# CLK_INPUT.net
KiCad netlist of a schematic drawn in Altium Designer
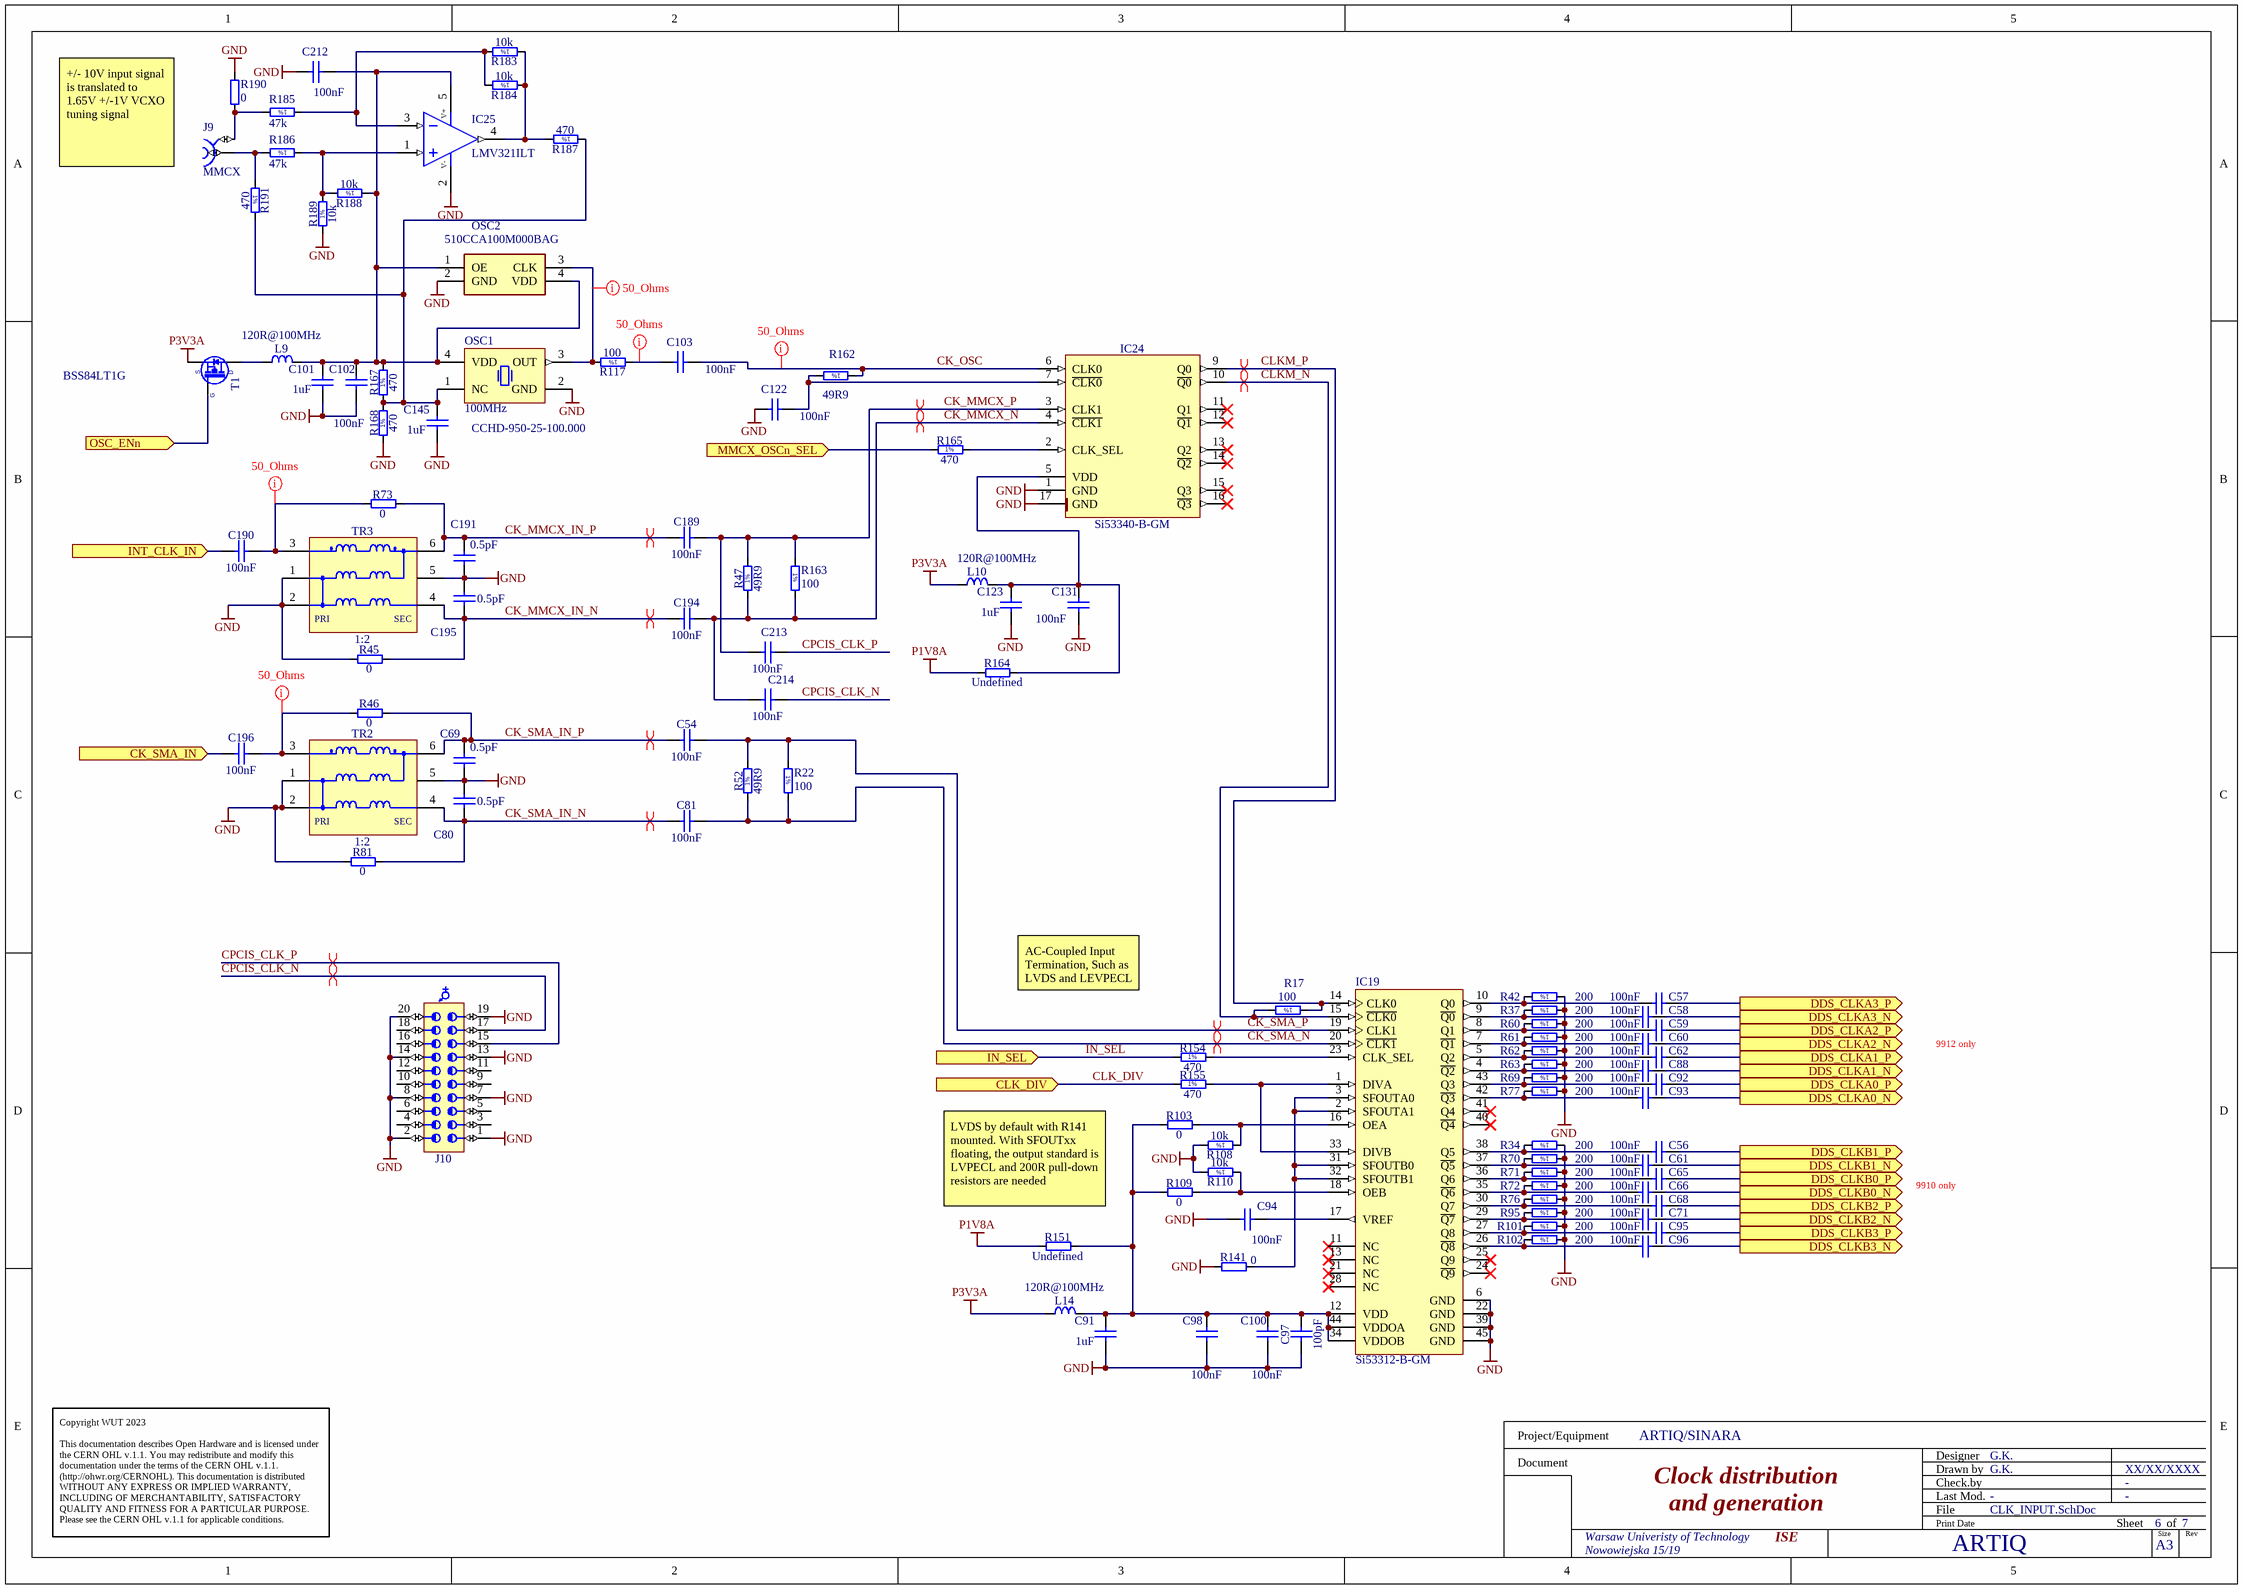
[diagram p0: CLK_INPUT.SchDoc]

(export (version "E")
  (design (tool "Eeschema 10.0.6"))
  (components
    (comp (ref "C54")
      (value "100nF")
      (footprint "CAPC1005X55N")
      (description "Non-polarised capacitor")
      (fields
        (field (name "PART NUMBER") "CC0402_100NF_16V_10%_X5R")
        (field (name "VOLTAGE") "16V")
        (field (name "AUTHOR") "CERN DEM JLC")
      )
      (libsource (lib "Capacitors") (part "Capacitor - non polarized"))
    )
    (comp (ref "C56")
      (value "100nF")
      (footprint "CAPC1005X55N")
      (description "Non-polarised capacitor")
      (fields
        (field (name "PART NUMBER") "CC0402_100NF_16V_10%_X5R")
        (field (name "VOLTAGE") "16V")
        (field (name "AUTHOR") "CERN DEM JLC")
      )
      (libsource (lib "Capacitors") (part "Capacitor - non polarized"))
    )
    (comp (ref "C57")
      (value "100nF")
      (footprint "CAPC1005X55N")
      (description "Non-polarised capacitor")
      (fields
        (field (name "PART NUMBER") "CC0402_100NF_16V_10%_X5R")
        (field (name "VOLTAGE") "16V")
        (field (name "AUTHOR") "CERN DEM JLC")
      )
      (libsource (lib "Capacitors") (part "Capacitor - non polarized"))
    )
    (comp (ref "C58")
      (value "100nF")
      (footprint "CAPC1005X55N")
      (description "Non-polarised capacitor")
      (fields
        (field (name "PART NUMBER") "CC0402_100NF_16V_10%_X5R")
        (field (name "VOLTAGE") "16V")
        (field (name "AUTHOR") "CERN DEM JLC")
      )
      (libsource (lib "Capacitors") (part "Capacitor - non polarized"))
    )
    (comp (ref "C59")
      (value "100nF")
      (footprint "CAPC1005X55N")
      (description "Non-polarised capacitor")
      (fields
        (field (name "PART NUMBER") "CC0402_100NF_16V_10%_X5R")
        (field (name "VOLTAGE") "16V")
        (field (name "AUTHOR") "CERN DEM JLC")
      )
      (libsource (lib "Capacitors") (part "Capacitor - non polarized"))
    )
    (comp (ref "C60")
      (value "100nF")
      (footprint "CAPC1005X55N")
      (description "Non-polarised capacitor")
      (fields
        (field (name "PART NUMBER") "CC0402_100NF_16V_10%_X5R")
        (field (name "VOLTAGE") "16V")
        (field (name "AUTHOR") "CERN DEM JLC")
      )
      (libsource (lib "Capacitors") (part "Capacitor - non polarized"))
    )
    (comp (ref "C61")
      (value "100nF")
      (footprint "CAPC1005X55N")
      (description "Non-polarised capacitor")
      (fields
        (field (name "PART NUMBER") "CC0402_100NF_16V_10%_X5R")
        (field (name "VOLTAGE") "16V")
        (field (name "AUTHOR") "CERN DEM JLC")
      )
      (libsource (lib "Capacitors") (part "Capacitor - non polarized"))
    )
    (comp (ref "C62")
      (value "100nF")
      (footprint "CAPC1005X55N")
      (description "Non-polarised capacitor")
      (fields
        (field (name "PART NUMBER") "CC0402_100NF_16V_10%_X5R")
        (field (name "VOLTAGE") "16V")
        (field (name "AUTHOR") "CERN DEM JLC")
      )
      (libsource (lib "Capacitors") (part "Capacitor - non polarized"))
    )
    (comp (ref "C65")
      (value "100nF")
      (footprint "CAPC1005X55N")
      (description "Non-polarised capacitor")
      (fields
        (field (name "PART NUMBER") "CC0402_100NF_16V_10%_X5R")
        (field (name "VOLTAGE") "16V")
        (field (name "AUTHOR") "CERN DEM JLC")
      )
      (libsource (lib "Capacitors") (part "Capacitor - non polarized"))
    )
    (comp (ref "C66")
      (value "100nF")
      (footprint "CAPC1005X55N")
      (description "Non-polarised capacitor")
      (fields
        (field (name "PART NUMBER") "CC0402_100NF_16V_10%_X5R")
        (field (name "VOLTAGE") "16V")
        (field (name "AUTHOR") "CERN DEM JLC")
      )
      (libsource (lib "Capacitors") (part "Capacitor - non polarized"))
    )
    (comp (ref "C68")
      (value "100nF")
      (footprint "CAPC1005X55N")
      (description "Non-polarised capacitor")
      (fields
        (field (name "PART NUMBER") "CC0402_100NF_16V_10%_X5R")
        (field (name "VOLTAGE") "16V")
        (field (name "AUTHOR") "CERN DEM JLC")
      )
      (libsource (lib "Capacitors") (part "Capacitor - non polarized"))
    )
    (comp (ref "C69")
      (value "0.5pF")
      (footprint "CAPC1005X50N")
      (description "Non-polarised capacitor")
      (fields
        (field (name "PART NUMBER") "CC0402_0.5PF_25V_0.05PF_AVX_04023J0R5ABSTR")
        (field (name "VOLTAGE") "25V")
        (field (name "AUTHOR") "CERN DEM JLC")
      )
      (libsource (lib "Capacitors") (part "Capacitor - non polarized"))
    )
    (comp (ref "C71")
      (value "100nF")
      (footprint "CAPC1005X55N")
      (description "Non-polarised capacitor")
      (fields
        (field (name "PART NUMBER") "CC0402_100NF_16V_10%_X5R")
        (field (name "VOLTAGE") "16V")
        (field (name "AUTHOR") "CERN DEM JLC")
      )
      (libsource (lib "Capacitors") (part "Capacitor - non polarized"))
    )
    (comp (ref "C80")
      (value "0.5pF")
      (footprint "CAPC1005X50N")
      (description "Non-polarised capacitor")
      (fields
        (field (name "PART NUMBER") "CC0402_0.5PF_25V_0.05PF_AVX_04023J0R5ABSTR")
        (field (name "VOLTAGE") "25V")
        (field (name "AUTHOR") "CERN DEM JLC")
      )
      (libsource (lib "Capacitors") (part "Capacitor - non polarized"))
    )
    (comp (ref "C81")
      (value "100nF")
      (footprint "CAPC1005X55N")
      (description "Non-polarised capacitor")
      (fields
        (field (name "PART NUMBER") "CC0402_100NF_16V_10%_X5R")
        (field (name "VOLTAGE") "16V")
        (field (name "AUTHOR") "CERN DEM JLC")
      )
      (libsource (lib "Capacitors") (part "Capacitor - non polarized"))
    )
    (comp (ref "C88")
      (value "100nF")
      (footprint "CAPC1005X55N")
      (description "Non-polarised capacitor")
      (fields
        (field (name "PART NUMBER") "CC0402_100NF_16V_10%_X5R")
        (field (name "VOLTAGE") "16V")
        (field (name "AUTHOR") "CERN DEM JLC")
      )
      (libsource (lib "Capacitors") (part "Capacitor - non polarized"))
    )
    (comp (ref "C91")
      (value "1uF")
      (footprint "CAPC1005X55N")
      (description "Non-polarised capacitor")
      (fields
        (field (name "PART NUMBER") "CC0402_1UF_16V_10%_X5R")
        (field (name "VOLTAGE") "16V")
        (field (name "AUTHOR") "CERN DEM JLC")
      )
      (libsource (lib "Capacitors") (part "Capacitor - non polarized"))
    )
    (comp (ref "C92")
      (value "100nF")
      (footprint "CAPC1005X55N")
      (description "Non-polarised capacitor")
      (fields
        (field (name "PART NUMBER") "CC0402_100NF_16V_10%_X5R")
        (field (name "VOLTAGE") "16V")
        (field (name "AUTHOR") "CERN DEM JLC")
      )
      (libsource (lib "Capacitors") (part "Capacitor - non polarized"))
    )
    (comp (ref "C93")
      (value "100nF")
      (footprint "CAPC1005X55N")
      (description "Non-polarised capacitor")
      (fields
        (field (name "PART NUMBER") "CC0402_100NF_16V_10%_X5R")
        (field (name "VOLTAGE") "16V")
        (field (name "AUTHOR") "CERN DEM JLC")
      )
      (libsource (lib "Capacitors") (part "Capacitor - non polarized"))
    )
    (comp (ref "C94")
      (value "100nF")
      (footprint "CAPC1005X55N")
      (description "Non-polarised capacitor")
      (fields
        (field (name "PART NUMBER") "CC0402_100NF_16V_10%_X5R")
        (field (name "VOLTAGE") "16V")
        (field (name "AUTHOR") "CERN DEM JLC")
      )
      (libsource (lib "Capacitors") (part "Capacitor - non polarized"))
    )
    (comp (ref "C95")
      (value "100nF")
      (footprint "CAPC1005X55N")
      (description "Non-polarised capacitor")
      (fields
        (field (name "PART NUMBER") "CC0402_100NF_16V_10%_X5R")
        (field (name "VOLTAGE") "16V")
        (field (name "AUTHOR") "CERN DEM JLC")
      )
      (libsource (lib "Capacitors") (part "Capacitor - non polarized"))
    )
    (comp (ref "C96")
      (value "100nF")
      (footprint "CAPC1005X55N")
      (description "Non-polarised capacitor")
      (fields
        (field (name "PART NUMBER") "CC0402_100NF_16V_10%_X5R")
        (field (name "VOLTAGE") "16V")
        (field (name "AUTHOR") "CERN DEM JLC")
      )
      (libsource (lib "Capacitors") (part "Capacitor - non polarized"))
    )
    (comp (ref "C97")
      (value "100pF")
      (footprint "CAPC1005X55N")
      (description "Non-polarised capacitor")
      (fields
        (field (name "PART NUMBER") "CC0402_100PF_50V_5%_C0G")
        (field (name "VOLTAGE") "50V")
        (field (name "AUTHOR") "CERN DEM JLC")
      )
      (libsource (lib "Capacitors") (part "Capacitor - non polarized"))
    )
    (comp (ref "C98")
      (value "100nF")
      (footprint "CAPC1005X55N")
      (description "Non-polarised capacitor")
      (fields
        (field (name "PART NUMBER") "CC0402_100NF_16V_10%_X5R")
        (field (name "VOLTAGE") "16V")
        (field (name "AUTHOR") "CERN DEM JLC")
      )
      (libsource (lib "Capacitors") (part "Capacitor - non polarized"))
    )
    (comp (ref "C100")
      (value "100nF")
      (footprint "CAPC1005X55N")
      (description "Non-polarised capacitor")
      (fields
        (field (name "PART NUMBER") "CC0402_100NF_16V_10%_X5R")
        (field (name "VOLTAGE") "16V")
        (field (name "AUTHOR") "CERN DEM JLC")
      )
      (libsource (lib "Capacitors") (part "Capacitor - non polarized"))
    )
    (comp (ref "C101")
      (value "1uF")
      (footprint "CAPC1005X55N")
      (description "Non-polarised capacitor")
      (fields
        (field (name "PART NUMBER") "CC0402_1UF_16V_10%_X5R")
        (field (name "VOLTAGE") "16V")
        (field (name "AUTHOR") "CERN DEM JLC")
      )
      (libsource (lib "Capacitors") (part "Capacitor - non polarized"))
    )
    (comp (ref "C102")
      (value "100nF")
      (footprint "CAPC1005X55N")
      (description "Non-polarised capacitor")
      (fields
        (field (name "PART NUMBER") "CC0402_100NF_16V_10%_X5R")
        (field (name "VOLTAGE") "16V")
        (field (name "AUTHOR") "CERN DEM JLC")
      )
      (libsource (lib "Capacitors") (part "Capacitor - non polarized"))
    )
    (comp (ref "C103")
      (value "100nF")
      (footprint "CAPC1005X55N")
      (description "Non-polarised capacitor")
      (fields
        (field (name "PART NUMBER") "CC0402_100NF_16V_10%_X5R")
        (field (name "VOLTAGE") "16V")
        (field (name "AUTHOR") "CERN DEM JLC")
      )
      (libsource (lib "Capacitors") (part "Capacitor - non polarized"))
    )
    (comp (ref "C122")
      (value "100nF")
      (footprint "CAPC1005X55N")
      (description "Non-polarised capacitor")
      (fields
        (field (name "PART NUMBER") "CC0402_100NF_16V_10%_X5R")
        (field (name "VOLTAGE") "16V")
        (field (name "AUTHOR") "CERN DEM JLC")
      )
      (libsource (lib "Capacitors") (part "Capacitor - non polarized"))
    )
    (comp (ref "C123")
      (value "1uF")
      (footprint "CAPC1005X55N")
      (description "Non-polarised capacitor")
      (fields
        (field (name "PART NUMBER") "CC0402_1UF_16V_10%_X5R")
        (field (name "VOLTAGE") "16V")
        (field (name "AUTHOR") "CERN DEM JLC")
      )
      (libsource (lib "Capacitors") (part "Capacitor - non polarized"))
    )
    (comp (ref "C131")
      (value "100nF")
      (footprint "CAPC1005X55N")
      (description "Non-polarised capacitor")
      (fields
        (field (name "PART NUMBER") "CC0402_100NF_16V_10%_X5R")
        (field (name "VOLTAGE") "16V")
        (field (name "AUTHOR") "CERN DEM JLC")
      )
      (libsource (lib "Capacitors") (part "Capacitor - non polarized"))
    )
    (comp (ref "C145")
      (value "1uF")
      (footprint "CAPC1005X55N")
      (description "Non-polarised capacitor")
      (fields
        (field (name "PART NUMBER") "CC0402_1UF_16V_10%_X5R")
        (field (name "VOLTAGE") "16V")
        (field (name "AUTHOR") "CERN DEM JLC")
      )
      (libsource (lib "Capacitors") (part "Capacitor - non polarized"))
    )
    (comp (ref "C189")
      (value "100nF")
      (footprint "CAPC1005X55N")
      (description "Non-polarised capacitor")
      (fields
        (field (name "PART NUMBER") "CC0402_100NF_16V_10%_X5R")
        (field (name "VOLTAGE") "16V")
        (field (name "AUTHOR") "CERN DEM JLC")
      )
      (libsource (lib "Capacitors") (part "Capacitor - non polarized"))
    )
    (comp (ref "C190")
      (value "100nF")
      (footprint "CAPC1005X55N")
      (description "Non-polarised capacitor")
      (fields
        (field (name "PART NUMBER") "CC0402_100NF_16V_10%_X5R")
        (field (name "VOLTAGE") "16V")
        (field (name "AUTHOR") "CERN DEM JLC")
      )
      (libsource (lib "Capacitors") (part "Capacitor - non polarized"))
    )
    (comp (ref "C191")
      (value "0.5pF")
      (footprint "CAPC1005X50N")
      (description "Non-polarised capacitor")
      (fields
        (field (name "PART NUMBER") "CC0402_0.5PF_25V_0.05PF_AVX_04023J0R5ABSTR")
        (field (name "VOLTAGE") "25V")
        (field (name "AUTHOR") "CERN DEM JLC")
      )
      (libsource (lib "Capacitors") (part "Capacitor - non polarized"))
    )
    (comp (ref "C194")
      (value "100nF")
      (footprint "CAPC1005X55N")
      (description "Non-polarised capacitor")
      (fields
        (field (name "PART NUMBER") "CC0402_100NF_16V_10%_X5R")
        (field (name "VOLTAGE") "16V")
        (field (name "AUTHOR") "CERN DEM JLC")
      )
      (libsource (lib "Capacitors") (part "Capacitor - non polarized"))
    )
    (comp (ref "C195")
      (value "0.5pF")
      (footprint "CAPC1005X50N")
      (description "Non-polarised capacitor")
      (fields
        (field (name "PART NUMBER") "CC0402_0.5PF_25V_0.05PF_AVX_04023J0R5ABSTR")
        (field (name "VOLTAGE") "25V")
        (field (name "AUTHOR") "CERN DEM JLC")
      )
      (libsource (lib "Capacitors") (part "Capacitor - non polarized"))
    )
    (comp (ref "C196")
      (value "100nF")
      (footprint "CAPC1005X55N")
      (description "Non-polarised capacitor")
      (fields
        (field (name "PART NUMBER") "CC0402_100NF_16V_10%_X5R")
        (field (name "VOLTAGE") "16V")
        (field (name "AUTHOR") "CERN DEM JLC")
      )
      (libsource (lib "Capacitors") (part "Capacitor - non polarized"))
    )
    (comp (ref "C212")
      (value "100nF")
      (footprint "CAPC1005X55N")
      (description "Non-polarised capacitor")
      (fields
        (field (name "PART NUMBER") "CC0402_100NF_16V_10%_X5R")
        (field (name "VOLTAGE") "16V")
        (field (name "AUTHOR") "CERN DEM JLC")
      )
      (libsource (lib "Capacitors") (part "Capacitor - non polarized"))
    )
    (comp (ref "C213")
      (value "100nF")
      (footprint "CAPC1005X55N")
      (description "Non-polarised capacitor")
      (fields
        (field (name "PART NUMBER") "CC0402_100NF_16V_10%_X5R")
        (field (name "VOLTAGE") "16V")
        (field (name "AUTHOR") "CERN DEM JLC")
      )
      (libsource (lib "Capacitors") (part "Capacitor - non polarized"))
    )
    (comp (ref "C214")
      (value "100nF")
      (footprint "CAPC1005X55N")
      (description "Non-polarised capacitor")
      (fields
        (field (name "PART NUMBER") "CC0402_100NF_16V_10%_X5R")
        (field (name "VOLTAGE") "16V")
        (field (name "AUTHOR") "CERN DEM JLC")
      )
      (libsource (lib "Capacitors") (part "Capacitor - non polarized"))
    )
    (comp (ref "IC19")
      (value "Si53312-B-GM")
      (footprint "SLAB-QFN-44-2800x2800TP_N")
      (fields (field (name "MANUFACTURER") "Silicon Labs"))
      (libsource (lib "Altium Content Vault") (part "SLAB-Si53312-QFN-44-45"))
    )
    (comp (ref "IC24")
      (value "Si53340-B-GM")
      (footprint "QFN50P300X300X90-17N-S175")
      (description "Low-Jitter LVDS Fanout Clock Buffers, 10-Output,  Any-Input, Any-Frequency up to 1250MHz")
      (fields (field (name "MANUFACTURER") "SILICON LABS") (field (name "AUTHOR") "CERN DEM MR"))
      (libsource (lib "ICs And Semiconductors") (part "Si53340"))
    )
    (comp (ref "IC25")
      (value "LMV321ILT")
      (footprint "SOT95P280X145-5N")
      (description "Operational Amplifier")
      (fields (field (name "MANUFACTURER") "ST MICROELECTRONICS") (field (name "AUTHOR") "CERN DEM MR"))
      (libsource (lib "ICs And Semiconductors") (part "Operational Amplifier Type10"))
    )
    (comp (ref "J9")
      (value "MMCX")
      (footprint "SAMTEC_MMCX-J-P-H-ST-TH1")
      (fields
        (field (name "PART NUMBER") "SAMTEC_MMCX-J-P-H-ST-TH1")
        (field (name "MANUFACTURER") "SAMTEC")
        (field (name "MANUFACTURER PART NUMBER") "MMCX-J-P-H-ST-TH1")
        (field (name "AUTHOR") "CERN DEM JLC")
      )
      (libsource (lib "Connectors") (part "Coax_1Female_1Shield"))
    )
    (comp (ref "J10")
      (value "~")
      (footprint "SAMTEC_LSS-110-01-L-DV-A")
      (description "Connector 20 Hermaphroditic")
      (fields
        (field (name "PART NUMBER") "SAMTEC_LSS-110-01-L-DV-A")
        (field (name "MANUFACTURER") "SAMTEC")
        (field (name "AUTHOR") "CERN DEM MR")
      )
      (libsource (lib "Connectors") (part "Connector 20 Hermaphroditic"))
    )
    (comp (ref "L9")
      (value "120R@100MHz")
      (footprint "INDC1608X95N")
      (description "Inductor")
      (fields
        (field (name "PART NUMBER") "IND0603_MURATA_BLM18PG121SN1D")
        (field (name "POWER") "2A")
        (field (name "AUTHOR") "CERN DEM BC")
      )
      (libsource (lib "Inductors & Transformers") (part "Inductor"))
    )
    (comp (ref "L10")
      (value "120R@100MHz")
      (footprint "INDC1608X95N")
      (description "Inductor")
      (fields
        (field (name "PART NUMBER") "IND0603_MURATA_BLM18PG121SN1D")
        (field (name "POWER") "2A")
        (field (name "AUTHOR") "CERN DEM BC")
      )
      (libsource (lib "Inductors & Transformers") (part "Inductor"))
    )
    (comp (ref "L14")
      (value "120R@100MHz")
      (footprint "INDC1608X95N")
      (description "Inductor")
      (fields
        (field (name "PART NUMBER") "IND0603_MURATA_BLM18PG121SN1D")
        (field (name "POWER") "2A")
        (field (name "AUTHOR") "CERN DEM BC")
      )
      (libsource (lib "Inductors & Transformers") (part "Inductor"))
    )
    (comp (ref "OSC1")
      (value "100MHz")
      (footprint "OSC_CRYSTEK_CCHD-950")
      (description "100MHz low noise oscillator")
      (fields
        (field (name "PART NUMBER") "OSC_100MHZ_CRYSTEK_CCHD-950-25-100.000")
        (field (name "MANUFACTURER") "CRYSTEK CRYSTAL")
        (field (name "MANUFACTURER PART NUMBER") "CCHD-950-25-100.000")
        (field (name "AUTHOR") "GK")
      )
      (libsource (lib "LIBRARY_SCH") (part "OSC_CCHD-950"))
    )
    (comp (ref "OSC2")
      (value "510CCA100M000BAG")
      (footprint "SamacSys:510CBA49M1520BAG")
      (description "Crystal or Oscillator")
      (fields (field (name "MOUSER PART NUMBER") "634-510CCA100M000BAG"))
      (libsource (lib "*") (part "510CCA100M000BAG"))
    )
    (comp (ref "R17")
      (value "100")
      (footprint "RESC1005X40N")
      (description "Resistor - 1%")
      (fields
        (field (name "PART NUMBER") "R0402_100R_1%_0.0625W_100PPM")
        (field (name "POWER") "0.0625W")
        (field (name "AUTHOR") "CERN DEM JLC")
      )
      (libsource (lib "Resistors") (part "Resistor - 1%"))
    )
    (comp (ref "R22")
      (value "100")
      (footprint "RESC1005X40N")
      (description "Resistor - 1%")
      (fields
        (field (name "PART NUMBER") "R0402_100R_1%_0.0625W_100PPM")
        (field (name "POWER") "0.0625W")
        (field (name "AUTHOR") "CERN DEM JLC")
      )
      (libsource (lib "Resistors") (part "Resistor - 1%"))
    )
    (comp (ref "R34")
      (value "200")
      (footprint "RESC1005X40N")
      (description "Resistor - 1%")
      (fields
        (field (name "PART NUMBER") "R0402_200R_1%_0.0625W_100PPM")
        (field (name "POWER") "0.0625W")
        (field (name "AUTHOR") "CERN DEM JLC")
      )
      (libsource (lib "Resistors") (part "Resistor - 1%"))
    )
    (comp (ref "R37")
      (value "200")
      (footprint "RESC1005X40N")
      (description "Resistor - 1%")
      (fields
        (field (name "PART NUMBER") "R0402_200R_1%_0.0625W_100PPM")
        (field (name "POWER") "0.0625W")
        (field (name "AUTHOR") "CERN DEM JLC")
      )
      (libsource (lib "Resistors") (part "Resistor - 1%"))
    )
    (comp (ref "R42")
      (value "200")
      (footprint "RESC1005X40N")
      (description "Resistor - 1%")
      (fields
        (field (name "PART NUMBER") "R0402_200R_1%_0.0625W_100PPM")
        (field (name "POWER") "0.0625W")
        (field (name "AUTHOR") "CERN DEM JLC")
      )
      (libsource (lib "Resistors") (part "Resistor - 1%"))
    )
    (comp (ref "R45")
      (value "0")
      (footprint "RESC1005X40N")
      (description "Resistor")
      (fields
        (field (name "PART NUMBER") "R0402_0R_JUMPER")
        (field (name "MANUFACTURER") "GENERIC")
        (field (name "AUTHOR") "CERN DEM JLC")
      )
      (libsource (lib "Resistors") (part "Resistor"))
    )
    (comp (ref "R46")
      (value "0")
      (footprint "RESC1005X40N")
      (description "Resistor")
      (fields
        (field (name "PART NUMBER") "R0402_0R_JUMPER")
        (field (name "MANUFACTURER") "GENERIC")
        (field (name "AUTHOR") "CERN DEM JLC")
      )
      (libsource (lib "Resistors") (part "Resistor"))
    )
    (comp (ref "R47")
      (value "49R9")
      (footprint "RESC1005X40N")
      (description "Resistor - 1%")
      (fields
        (field (name "PART NUMBER") "R0402_49R9_1%_0.0625W_100PPM")
        (field (name "POWER") "0.0625W")
        (field (name "AUTHOR") "CERN DEM JLC")
      )
      (libsource (lib "Resistors") (part "Resistor - 1%"))
    )
    (comp (ref "R52")
      (value "49R9")
      (footprint "RESC1005X40N")
      (description "Resistor - 1%")
      (fields
        (field (name "PART NUMBER") "R0402_49R9_1%_0.0625W_100PPM")
        (field (name "POWER") "0.0625W")
        (field (name "AUTHOR") "CERN DEM JLC")
      )
      (libsource (lib "Resistors") (part "Resistor - 1%"))
    )
    (comp (ref "R60")
      (value "200")
      (footprint "RESC1005X40N")
      (description "Resistor - 1%")
      (fields
        (field (name "PART NUMBER") "R0402_200R_1%_0.0625W_100PPM")
        (field (name "POWER") "0.0625W")
        (field (name "AUTHOR") "CERN DEM JLC")
      )
      (libsource (lib "Resistors") (part "Resistor - 1%"))
    )
    (comp (ref "R61")
      (value "200")
      (footprint "RESC1005X40N")
      (description "Resistor - 1%")
      (fields
        (field (name "PART NUMBER") "R0402_200R_1%_0.0625W_100PPM")
        (field (name "POWER") "0.0625W")
        (field (name "AUTHOR") "CERN DEM JLC")
      )
      (libsource (lib "Resistors") (part "Resistor - 1%"))
    )
    (comp (ref "R62")
      (value "200")
      (footprint "RESC1005X40N")
      (description "Resistor - 1%")
      (fields
        (field (name "PART NUMBER") "R0402_200R_1%_0.0625W_100PPM")
        (field (name "POWER") "0.0625W")
        (field (name "AUTHOR") "CERN DEM JLC")
      )
      (libsource (lib "Resistors") (part "Resistor - 1%"))
    )
    (comp (ref "R63")
      (value "200")
      (footprint "RESC1005X40N")
      (description "Resistor - 1%")
      (fields
        (field (name "PART NUMBER") "R0402_200R_1%_0.0625W_100PPM")
        (field (name "POWER") "0.0625W")
        (field (name "AUTHOR") "CERN DEM JLC")
      )
      (libsource (lib "Resistors") (part "Resistor - 1%"))
    )
    (comp (ref "R69")
      (value "200")
      (footprint "RESC1005X40N")
      (description "Resistor - 1%")
      (fields
        (field (name "PART NUMBER") "R0402_200R_1%_0.0625W_100PPM")
        (field (name "POWER") "0.0625W")
        (field (name "AUTHOR") "CERN DEM JLC")
      )
      (libsource (lib "Resistors") (part "Resistor - 1%"))
    )
    (comp (ref "R70")
      (value "200")
      (footprint "RESC1005X40N")
      (description "Resistor - 1%")
      (fields
        (field (name "PART NUMBER") "R0402_200R_1%_0.0625W_100PPM")
        (field (name "POWER") "0.0625W")
        (field (name "AUTHOR") "CERN DEM JLC")
      )
      (libsource (lib "Resistors") (part "Resistor - 1%"))
    )
    (comp (ref "R71")
      (value "200")
      (footprint "RESC1005X40N")
      (description "Resistor - 1%")
      (fields
        (field (name "PART NUMBER") "R0402_200R_1%_0.0625W_100PPM")
        (field (name "POWER") "0.0625W")
        (field (name "AUTHOR") "CERN DEM JLC")
      )
      (libsource (lib "Resistors") (part "Resistor - 1%"))
    )
    (comp (ref "R72")
      (value "200")
      (footprint "RESC1005X40N")
      (description "Resistor - 1%")
      (fields
        (field (name "PART NUMBER") "R0402_200R_1%_0.0625W_100PPM")
        (field (name "POWER") "0.0625W")
        (field (name "AUTHOR") "CERN DEM JLC")
      )
      (libsource (lib "Resistors") (part "Resistor - 1%"))
    )
    (comp (ref "R73")
      (value "0")
      (footprint "RESC1005X40N")
      (description "Resistor")
      (fields
        (field (name "PART NUMBER") "R0402_0R_JUMPER")
        (field (name "MANUFACTURER") "GENERIC")
        (field (name "AUTHOR") "CERN DEM JLC")
      )
      (libsource (lib "Resistors") (part "Resistor"))
    )
    (comp (ref "R76")
      (value "200")
      (footprint "RESC1005X40N")
      (description "Resistor - 1%")
      (fields
        (field (name "PART NUMBER") "R0402_200R_1%_0.0625W_100PPM")
        (field (name "POWER") "0.0625W")
        (field (name "AUTHOR") "CERN DEM JLC")
      )
      (libsource (lib "Resistors") (part "Resistor - 1%"))
    )
    (comp (ref "R77")
      (value "200")
      (footprint "RESC1005X40N")
      (description "Resistor - 1%")
      (fields
        (field (name "PART NUMBER") "R0402_200R_1%_0.0625W_100PPM")
        (field (name "POWER") "0.0625W")
        (field (name "AUTHOR") "CERN DEM JLC")
      )
      (libsource (lib "Resistors") (part "Resistor - 1%"))
    )
    (comp (ref "R81")
      (value "0")
      (footprint "RESC1005X40N")
      (description "Resistor")
      (fields
        (field (name "PART NUMBER") "R0402_0R_JUMPER")
        (field (name "MANUFACTURER") "GENERIC")
        (field (name "AUTHOR") "CERN DEM JLC")
      )
      (libsource (lib "Resistors") (part "Resistor"))
    )
    (comp (ref "R95")
      (value "200")
      (footprint "RESC1005X40N")
      (description "Resistor - 1%")
      (fields
        (field (name "PART NUMBER") "R0402_200R_1%_0.0625W_100PPM")
        (field (name "POWER") "0.0625W")
        (field (name "AUTHOR") "CERN DEM JLC")
      )
      (libsource (lib "Resistors") (part "Resistor - 1%"))
    )
    (comp (ref "R101")
      (value "200")
      (footprint "RESC1005X40N")
      (description "Resistor - 1%")
      (fields
        (field (name "PART NUMBER") "R0402_200R_1%_0.0625W_100PPM")
        (field (name "POWER") "0.0625W")
        (field (name "AUTHOR") "CERN DEM JLC")
      )
      (libsource (lib "Resistors") (part "Resistor - 1%"))
    )
    (comp (ref "R102")
      (value "200")
      (footprint "RESC1005X40N")
      (description "Resistor - 1%")
      (fields
        (field (name "PART NUMBER") "R0402_200R_1%_0.0625W_100PPM")
        (field (name "POWER") "0.0625W")
        (field (name "AUTHOR") "CERN DEM JLC")
      )
      (libsource (lib "Resistors") (part "Resistor - 1%"))
    )
    (comp (ref "R103")
      (value "0")
      (footprint "RESC1608X55N")
      (description "Resistor")
      (fields
        (field (name "PART NUMBER") "R0603_0R_JUMPER")
        (field (name "MANUFACTURER") "GENERIC")
        (field (name "AUTHOR") "CERN DEM JLC")
      )
      (libsource (lib "Resistors") (part "Resistor"))
    )
    (comp (ref "R108")
      (value "10k")
      (footprint "RESC1005X40N")
      (description "Resistor - 1%")
      (fields
        (field (name "PART NUMBER") "R0402_10K_1%_0.0625W_100PPM")
        (field (name "POWER") "0.0625W")
        (field (name "AUTHOR") "CERN DEM JLC")
      )
      (libsource (lib "Resistors") (part "Resistor - 1%"))
    )
    (comp (ref "R109")
      (value "0")
      (footprint "RESC1608X55N")
      (description "Resistor")
      (fields
        (field (name "PART NUMBER") "R0603_0R_JUMPER")
        (field (name "MANUFACTURER") "GENERIC")
        (field (name "AUTHOR") "CERN DEM JLC")
      )
      (libsource (lib "Resistors") (part "Resistor"))
    )
    (comp (ref "R110")
      (value "10k")
      (footprint "RESC1005X40N")
      (description "Resistor - 1%")
      (fields
        (field (name "PART NUMBER") "R0402_10K_1%_0.0625W_100PPM")
        (field (name "POWER") "0.0625W")
        (field (name "AUTHOR") "CERN DEM JLC")
      )
      (libsource (lib "Resistors") (part "Resistor - 1%"))
    )
    (comp (ref "R117")
      (value "100")
      (footprint "RESC1005X40N")
      (description "Resistor - 1%")
      (fields
        (field (name "PART NUMBER") "R0402_100R_1%_0.0625W_100PPM")
        (field (name "POWER") "0.0625W")
        (field (name "AUTHOR") "CERN DEM JLC")
      )
      (libsource (lib "Resistors") (part "Resistor - 1%"))
    )
    (comp (ref "R141")
      (value "0")
      (footprint "RESC1608X55N")
      (description "Resistor")
      (fields
        (field (name "PART NUMBER") "R0603_0R_JUMPER")
        (field (name "MANUFACTURER") "GENERIC")
        (field (name "AUTHOR") "CERN DEM JLC")
      )
      (libsource (lib "Resistors") (part "Resistor"))
    )
    (comp (ref "R151")
      (value "Undefined")
      (footprint "RESC1608X55N")
      (description "Resistor")
      (fields (field (name "PART NUMBER") "R0603_NO-VALUE") (field (name "AUTHOR") "CERN DEM JLC"))
      (libsource (lib "Resistors") (part "Resistor"))
    )
    (comp (ref "R154")
      (value "470")
      (footprint "RESC1005X40N")
      (description "Resistor - 1%")
      (fields
        (field (name "PART NUMBER") "R0402_470R_1%_0.0625W_100PPM")
        (field (name "POWER") "0.0625W")
        (field (name "AUTHOR") "CERN DEM JLC")
      )
      (libsource (lib "Resistors") (part "Resistor - 1%"))
    )
    (comp (ref "R155")
      (value "470")
      (footprint "RESC1005X40N")
      (description "Resistor - 1%")
      (fields
        (field (name "PART NUMBER") "R0402_470R_1%_0.0625W_100PPM")
        (field (name "POWER") "0.0625W")
        (field (name "AUTHOR") "CERN DEM JLC")
      )
      (libsource (lib "Resistors") (part "Resistor - 1%"))
    )
    (comp (ref "R162")
      (value "49R9")
      (footprint "RESC1005X40N")
      (description "Resistor - 1%")
      (fields
        (field (name "PART NUMBER") "R0402_49R9_1%_0.0625W_100PPM")
        (field (name "POWER") "0.0625W")
        (field (name "AUTHOR") "CERN DEM JLC")
      )
      (libsource (lib "Resistors") (part "Resistor - 1%"))
    )
    (comp (ref "R163")
      (value "100")
      (footprint "RESC1005X40N")
      (description "Resistor - 1%")
      (fields
        (field (name "PART NUMBER") "R0402_100R_1%_0.0625W_100PPM")
        (field (name "POWER") "0.0625W")
        (field (name "AUTHOR") "CERN DEM JLC")
      )
      (libsource (lib "Resistors") (part "Resistor - 1%"))
    )
    (comp (ref "R164")
      (value "Undefined")
      (footprint "RESC1608X55N")
      (description "Resistor")
      (fields (field (name "PART NUMBER") "R0603_NO-VALUE") (field (name "AUTHOR") "CERN DEM JLC"))
      (libsource (lib "Resistors") (part "Resistor"))
    )
    (comp (ref "R165")
      (value "470")
      (footprint "RESC1005X40N")
      (description "Resistor - 1%")
      (fields
        (field (name "PART NUMBER") "R0402_470R_1%_0.0625W_100PPM")
        (field (name "POWER") "0.0625W")
        (field (name "AUTHOR") "CERN DEM JLC")
      )
      (libsource (lib "Resistors") (part "Resistor - 1%"))
    )
    (comp (ref "R167")
      (value "470")
      (footprint "RESC1005X40N")
      (description "Resistor - 1%")
      (fields
        (field (name "PART NUMBER") "R0402_470R_1%_0.0625W_100PPM")
        (field (name "POWER") "0.0625W")
        (field (name "AUTHOR") "CERN DEM JLC")
      )
      (libsource (lib "Resistors") (part "Resistor - 1%"))
    )
    (comp (ref "R168")
      (value "470")
      (footprint "RESC1005X40N")
      (description "Resistor - 1%")
      (fields
        (field (name "PART NUMBER") "R0402_470R_1%_0.0625W_100PPM")
        (field (name "POWER") "0.0625W")
        (field (name "AUTHOR") "CERN DEM JLC")
      )
      (libsource (lib "Resistors") (part "Resistor - 1%"))
    )
    (comp (ref "R183")
      (value "10k")
      (footprint "RESC1005X40N")
      (description "Resistor - 1%")
      (fields
        (field (name "PART NUMBER") "R0402_10K_1%_0.0625W_100PPM")
        (field (name "POWER") "0.0625W")
        (field (name "AUTHOR") "CERN DEM JLC")
      )
      (libsource (lib "Resistors") (part "Resistor - 1%"))
    )
    (comp (ref "R184")
      (value "10k")
      (footprint "RESC1005X40N")
      (description "Resistor - 1%")
      (fields
        (field (name "PART NUMBER") "R0402_10K_1%_0.0625W_100PPM")
        (field (name "POWER") "0.0625W")
        (field (name "AUTHOR") "CERN DEM JLC")
      )
      (libsource (lib "Resistors") (part "Resistor - 1%"))
    )
    (comp (ref "R185")
      (value "47k")
      (footprint "RESC1608X55N")
      (description "Resistor - 1%")
      (fields
        (field (name "PART NUMBER") "R0603_47K_1%_0.1W_100PPM")
        (field (name "POWER") "0.1W")
        (field (name "AUTHOR") "CERN DEM JLC")
      )
      (libsource (lib "Resistors") (part "Resistor - 1%"))
    )
    (comp (ref "R186")
      (value "47k")
      (footprint "RESC1608X55N")
      (description "Resistor - 1%")
      (fields
        (field (name "PART NUMBER") "R0603_47K_1%_0.1W_100PPM")
        (field (name "POWER") "0.1W")
        (field (name "AUTHOR") "CERN DEM JLC")
      )
      (libsource (lib "Resistors") (part "Resistor - 1%"))
    )
    (comp (ref "R187")
      (value "470")
      (footprint "RESC1005X40N")
      (description "Resistor - 1%")
      (fields
        (field (name "PART NUMBER") "R0402_470R_1%_0.0625W_100PPM")
        (field (name "POWER") "0.0625W")
        (field (name "AUTHOR") "CERN DEM JLC")
      )
      (libsource (lib "Resistors") (part "Resistor - 1%"))
    )
    (comp (ref "R188")
      (value "10k")
      (footprint "RESC1005X40N")
      (description "Resistor - 1%")
      (fields
        (field (name "PART NUMBER") "R0402_10K_1%_0.0625W_100PPM")
        (field (name "POWER") "0.0625W")
        (field (name "AUTHOR") "CERN DEM JLC")
      )
      (libsource (lib "Resistors") (part "Resistor - 1%"))
    )
    (comp (ref "R189")
      (value "10k")
      (footprint "RESC1005X40N")
      (description "Resistor - 1%")
      (fields
        (field (name "PART NUMBER") "R0402_10K_1%_0.0625W_100PPM")
        (field (name "POWER") "0.0625W")
        (field (name "AUTHOR") "CERN DEM JLC")
      )
      (libsource (lib "Resistors") (part "Resistor - 1%"))
    )
    (comp (ref "R190")
      (value "0")
      (footprint "RESC1005X40N")
      (description "Resistor")
      (fields
        (field (name "PART NUMBER") "R0402_0R_JUMPER")
        (field (name "MANUFACTURER") "GENERIC")
        (field (name "AUTHOR") "CERN DEM JLC")
      )
      (libsource (lib "Resistors") (part "Resistor"))
    )
    (comp (ref "R191")
      (value "470")
      (footprint "RESC1005X40N")
      (description "Resistor - 1%")
      (fields
        (field (name "PART NUMBER") "R0402_470R_1%_0.0625W_100PPM")
        (field (name "POWER") "0.0625W")
        (field (name "AUTHOR") "CERN DEM JLC")
      )
      (libsource (lib "Resistors") (part "Resistor - 1%"))
    )
    (comp (ref "T1")
      (value "BSS84LT1G")
      (footprint "SOT95P240X110-3N")
      (description "P-CHANNEL MOSFET WITH DIODE")
      (fields (field (name "MANUFACTURER") "ON SEMICONDUCTOR") (field (name "AUTHOR") "CERN DEM JLC"))
      (libsource (lib "ICs And Semiconductors") (part "P-MOSFET-D 1G 2S 3D"))
    )
    (comp (ref "TR2")
      (value "1:2")
      (footprint "XFMR_MINI-CIRCUITS_DB1627")
      (description "50 OHMS 10 to 4000 MHz RF Transformer")
      (fields
        (field (name "PART NUMBER") "XFMR_MINI-CIRCUITS_TCM2-43X+")
        (field (name "POWER") "0.4W")
        (field (name "AUTHOR") "CERN DEM BC")
      )
      (libsource (lib "Inductors & Transformers") (part "XFMR_MINI-CIRCUITS_TCM2-43X"))
    )
    (comp (ref "TR3")
      (value "1:2")
      (footprint "XFMR_MINI-CIRCUITS_DB1627")
      (description "50 OHMS 10 to 4000 MHz RF Transformer")
      (fields
        (field (name "PART NUMBER") "XFMR_MINI-CIRCUITS_TCM2-43X+")
        (field (name "POWER") "0.4W")
        (field (name "AUTHOR") "CERN DEM BC")
      )
      (libsource (lib "Inductors & Transformers") (part "XFMR_MINI-CIRCUITS_TCM2-43X"))
    )
  )
  (nets
    (net (code "1") (name "/CK_MMCX_IN_N") (class "Default")
      (node (ref "C194") (pin "1") (pinfunction "1_1") (pintype "passive"))
      (node (ref "C195") (pin "1") (pinfunction "1_1") (pintype "passive"))
      (node (ref "R45") (pin "2") (pinfunction "2_2") (pintype "passive"))
      (node (ref "TR3") (pin "4") (pinfunction "S1_4") (pintype "passive"))
    )
    (net (code "2") (name "/CK_MMCX_IN_P") (class "Default")
      (node (ref "C189") (pin "1") (pinfunction "1_1") (pintype "passive"))
      (node (ref "C191") (pin "2") (pinfunction "2_2") (pintype "passive"))
      (node (ref "R73") (pin "2") (pinfunction "2_2") (pintype "passive"))
      (node (ref "TR3") (pin "6") (pinfunction "S1_6") (pintype "passive"))
    )
    (net (code "3") (name "/CK_MMCX_N") (class "Default")
      (node (ref "C194") (pin "2") (pinfunction "2_2") (pintype "passive"))
      (node (ref "C214") (pin "1") (pinfunction "1_1") (pintype "passive"))
      (node (ref "IC24") (pin "4") (pinfunction "~{CLK1}_4") (pintype "input"))
      (node (ref "R163") (pin "2") (pinfunction "2_2") (pintype "passive"))
      (node (ref "R47") (pin "1") (pinfunction "1_1") (pintype "passive"))
    )
    (net (code "4") (name "/CK_MMCX_P") (class "Default")
      (node (ref "C189") (pin "2") (pinfunction "2_2") (pintype "passive"))
      (node (ref "C213") (pin "1") (pinfunction "1_1") (pintype "passive"))
      (node (ref "IC24") (pin "3") (pinfunction "CLK1_3") (pintype "input"))
      (node (ref "R163") (pin "1") (pinfunction "1_1") (pintype "passive"))
      (node (ref "R47") (pin "2") (pinfunction "2_2") (pintype "passive"))
    )
    (net (code "5") (name "/CK_OSC") (class "Default")
      (node (ref "C103") (pin "1") (pinfunction "1_1") (pintype "passive"))
      (node (ref "IC24") (pin "6") (pinfunction "CLK0_6") (pintype "input"))
      (node (ref "R162") (pin "1") (pinfunction "1_1") (pintype "passive"))
    )
    (net (code "6") (name "/CK_SMA_IN") (class "Default")
      (node (ref "C196") (pin "1") (pinfunction "1_1") (pintype "passive"))
    )
    (net (code "7") (name "/CK_SMA_IN_N") (class "Default")
      (node (ref "C80") (pin "1") (pinfunction "1_1") (pintype "passive"))
      (node (ref "C81") (pin "1") (pinfunction "1_1") (pintype "passive"))
      (node (ref "R81") (pin "2") (pinfunction "2_2") (pintype "passive"))
      (node (ref "TR2") (pin "4") (pinfunction "S1_4") (pintype "passive"))
    )
    (net (code "8") (name "/CK_SMA_IN_P") (class "Default")
      (node (ref "C54") (pin "1") (pinfunction "1_1") (pintype "passive"))
      (node (ref "C69") (pin "2") (pinfunction "2_2") (pintype "passive"))
      (node (ref "R46") (pin "2") (pinfunction "2_2") (pintype "passive"))
      (node (ref "TR2") (pin "6") (pinfunction "S1_6") (pintype "passive"))
    )
    (net (code "9") (name "/CK_SMA_N") (class "Default")
      (node (ref "C81") (pin "2") (pinfunction "2_2") (pintype "passive"))
      (node (ref "IC19") (pin "20") (pinfunction "~{CLK1}_20") (pintype "input"))
      (node (ref "R22") (pin "2") (pinfunction "2_2") (pintype "passive"))
      (node (ref "R52") (pin "1") (pinfunction "1_1") (pintype "passive"))
    )
    (net (code "10") (name "/CK_SMA_P") (class "Default")
      (node (ref "C54") (pin "2") (pinfunction "2_2") (pintype "passive"))
      (node (ref "IC19") (pin "19") (pinfunction "CLK1_19") (pintype "input"))
      (node (ref "R22") (pin "1") (pinfunction "1_1") (pintype "passive"))
      (node (ref "R52") (pin "2") (pinfunction "2_2") (pintype "passive"))
    )
    (net (code "11") (name "/CLKM_N") (class "Default")
      (node (ref "IC19") (pin "15") (pinfunction "~{CLK0}_15") (pintype "input"))
      (node (ref "IC24") (pin "10") (pinfunction "~{Q0}_10") (pintype "output"))
      (node (ref "R17") (pin "2") (pinfunction "2_2") (pintype "passive"))
    )
    (net (code "12") (name "/CLKM_P") (class "Default")
      (node (ref "IC19") (pin "14") (pinfunction "CLK0_14") (pintype "input"))
      (node (ref "IC24") (pin "9") (pinfunction "Q0_9") (pintype "output"))
      (node (ref "R17") (pin "1") (pinfunction "1_1") (pintype "passive"))
    )
    (net (code "13") (name "/CLK_DIV") (class "Default")
      (node (ref "R155") (pin "1") (pinfunction "1_1") (pintype "passive"))
    )
    (net (code "14") (name "/CPCIS_CLK_N") (class "Default")
      (node (ref "C214") (pin "2") (pinfunction "2_2") (pintype "passive"))
      (node (ref "J10") (pin "17") (pinfunction "17_17") (pintype "bidirectional"))
    )
    (net (code "15") (name "/CPCIS_CLK_P") (class "Default")
      (node (ref "C213") (pin "2") (pinfunction "2_2") (pintype "passive"))
      (node (ref "J10") (pin "15") (pinfunction "15_15") (pintype "bidirectional"))
    )
    (net (code "16") (name "/DDS_CLKA0_N") (class "Default")
      (node (ref "C93") (pin "1") (pinfunction "1_1") (pintype "passive"))
    )
    (net (code "17") (name "/DDS_CLKA0_P") (class "Default")
      (node (ref "C92") (pin "1") (pinfunction "1_1") (pintype "passive"))
    )
    (net (code "18") (name "/DDS_CLKA1_N") (class "Default")
      (node (ref "C88") (pin "1") (pinfunction "1_1") (pintype "passive"))
    )
    (net (code "19") (name "/DDS_CLKA1_P") (class "Default")
      (node (ref "C62") (pin "1") (pinfunction "1_1") (pintype "passive"))
    )
    (net (code "20") (name "/DDS_CLKA2_N") (class "Default")
      (node (ref "C60") (pin "1") (pinfunction "1_1") (pintype "passive"))
    )
    (net (code "21") (name "/DDS_CLKA2_P") (class "Default")
      (node (ref "C59") (pin "1") (pinfunction "1_1") (pintype "passive"))
    )
    (net (code "22") (name "/DDS_CLKA3_N") (class "Default")
      (node (ref "C58") (pin "1") (pinfunction "1_1") (pintype "passive"))
    )
    (net (code "23") (name "/DDS_CLKA3_P") (class "Default")
      (node (ref "C57") (pin "1") (pinfunction "1_1") (pintype "passive"))
    )
    (net (code "24") (name "/DDS_CLKB0_N") (class "Default")
      (node (ref "C66") (pin "1") (pinfunction "1_1") (pintype "passive"))
    )
    (net (code "25") (name "/DDS_CLKB0_P") (class "Default")
      (node (ref "C65") (pin "1") (pinfunction "1_1") (pintype "passive"))
    )
    (net (code "26") (name "/DDS_CLKB1_N") (class "Default")
      (node (ref "C61") (pin "1") (pinfunction "1_1") (pintype "passive"))
    )
    (net (code "27") (name "/DDS_CLKB1_P") (class "Default")
      (node (ref "C56") (pin "1") (pinfunction "1_1") (pintype "passive"))
    )
    (net (code "28") (name "/DDS_CLKB2_N") (class "Default")
      (node (ref "C71") (pin "1") (pinfunction "1_1") (pintype "passive"))
    )
    (net (code "29") (name "/DDS_CLKB2_P") (class "Default")
      (node (ref "C68") (pin "1") (pinfunction "1_1") (pintype "passive"))
    )
    (net (code "30") (name "/DDS_CLKB3_N") (class "Default")
      (node (ref "C96") (pin "1") (pinfunction "1_1") (pintype "passive"))
    )
    (net (code "31") (name "/DDS_CLKB3_P") (class "Default")
      (node (ref "C95") (pin "1") (pinfunction "1_1") (pintype "passive"))
    )
    (net (code "32") (name "/INT_CLK_IN") (class "Default")
      (node (ref "C190") (pin "1") (pinfunction "1_1") (pintype "passive"))
    )
    (net (code "33") (name "/IN_SEL") (class "Default")
      (node (ref "R154") (pin "1") (pinfunction "1_1") (pintype "passive"))
    )
    (net (code "34") (name "/MMCX_OSCn_SEL") (class "Default")
      (node (ref "R165") (pin "1") (pinfunction "1_1") (pintype "passive"))
    )
    (net (code "35") (name "/OSC_ENn") (class "Default")
      (node (ref "T1") (pin "1") (pinfunction "G_1") (pintype "passive"))
    )
    (net (code "36") (name "GND") (class "Default")
      (node (ref "C100") (pin "1") (pinfunction "1_1") (pintype "passive"))
      (node (ref "C101") (pin "1") (pinfunction "1_1") (pintype "passive"))
      (node (ref "C102") (pin "1") (pinfunction "1_1") (pintype "passive"))
      (node (ref "C122") (pin "2") (pinfunction "2_2") (pintype "passive"))
      (node (ref "C123") (pin "1") (pinfunction "1_1") (pintype "passive"))
      (node (ref "C131") (pin "1") (pinfunction "1_1") (pintype "passive"))
      (node (ref "C145") (pin "1") (pinfunction "1_1") (pintype "passive"))
      (node (ref "C191") (pin "1") (pinfunction "1_1") (pintype "passive"))
      (node (ref "C195") (pin "2") (pinfunction "2_2") (pintype "passive"))
      (node (ref "C212") (pin "2") (pinfunction "2_2") (pintype "passive"))
      (node (ref "C69") (pin "1") (pinfunction "1_1") (pintype "passive"))
      (node (ref "C80") (pin "2") (pinfunction "2_2") (pintype "passive"))
      (node (ref "C91") (pin "1") (pinfunction "1_1") (pintype "passive"))
      (node (ref "C94") (pin "1") (pinfunction "1_1") (pintype "passive"))
      (node (ref "C97") (pin "1") (pinfunction "1_1") (pintype "passive"))
      (node (ref "C98") (pin "1") (pinfunction "1_1") (pintype "passive"))
      (node (ref "IC19") (pin "22") (pinfunction "GND_22") (pintype "power_in"))
      (node (ref "IC19") (pin "39") (pinfunction "GND_39") (pintype "power_in"))
      (node (ref "IC19") (pin "45") (pinfunction "GND_45") (pintype "power_in"))
      (node (ref "IC19") (pin "6") (pinfunction "GND_6") (pintype "power_in"))
      (node (ref "IC24") (pin "1") (pinfunction "GND_1") (pintype "power_in"))
      (node (ref "IC24") (pin "17") (pinfunction "GND_17") (pintype "power_in"))
      (node (ref "IC25") (pin "2") (pinfunction "V-_2") (pintype "power_in"))
      (node (ref "J10") (pin "1") (pinfunction "1_1") (pintype "bidirectional"))
      (node (ref "J10") (pin "13") (pinfunction "13_13") (pintype "bidirectional"))
      (node (ref "J10") (pin "14") (pinfunction "14_14") (pintype "bidirectional"))
      (node (ref "J10") (pin "19") (pinfunction "19_19") (pintype "bidirectional"))
      (node (ref "J10") (pin "2") (pinfunction "2_2") (pintype "bidirectional"))
      (node (ref "J10") (pin "20") (pinfunction "20_20") (pintype "bidirectional"))
      (node (ref "J10") (pin "7") (pinfunction "7_7") (pintype "bidirectional"))
      (node (ref "J10") (pin "8") (pinfunction "8_8") (pintype "bidirectional"))
      (node (ref "OSC1") (pin "2") (pinfunction "GND_2") (pintype "power_in"))
      (node (ref "OSC2") (pin "2") (pinfunction "GND_2") (pintype "passive"))
      (node (ref "R101") (pin "1") (pinfunction "1_1") (pintype "passive"))
      (node (ref "R102") (pin "1") (pinfunction "1_1") (pintype "passive"))
      (node (ref "R108") (pin "2") (pinfunction "2_2") (pintype "passive"))
      (node (ref "R110") (pin "2") (pinfunction "2_2") (pintype "passive"))
      (node (ref "R141") (pin "1") (pinfunction "1_1") (pintype "passive"))
      (node (ref "R168") (pin "1") (pinfunction "1_1") (pintype "passive"))
      (node (ref "R189") (pin "1") (pinfunction "1_1") (pintype "passive"))
      (node (ref "R190") (pin "2") (pinfunction "2_2") (pintype "passive"))
      (node (ref "R34") (pin "1") (pinfunction "1_1") (pintype "passive"))
      (node (ref "R37") (pin "1") (pinfunction "1_1") (pintype "passive"))
      (node (ref "R42") (pin "1") (pinfunction "1_1") (pintype "passive"))
      (node (ref "R45") (pin "1") (pinfunction "1_1") (pintype "passive"))
      (node (ref "R60") (pin "1") (pinfunction "1_1") (pintype "passive"))
      (node (ref "R61") (pin "1") (pinfunction "1_1") (pintype "passive"))
      (node (ref "R62") (pin "1") (pinfunction "1_1") (pintype "passive"))
      (node (ref "R63") (pin "1") (pinfunction "1_1") (pintype "passive"))
      (node (ref "R69") (pin "1") (pinfunction "1_1") (pintype "passive"))
      (node (ref "R70") (pin "1") (pinfunction "1_1") (pintype "passive"))
      (node (ref "R71") (pin "1") (pinfunction "1_1") (pintype "passive"))
      (node (ref "R72") (pin "1") (pinfunction "1_1") (pintype "passive"))
      (node (ref "R76") (pin "1") (pinfunction "1_1") (pintype "passive"))
      (node (ref "R77") (pin "1") (pinfunction "1_1") (pintype "passive"))
      (node (ref "R81") (pin "1") (pinfunction "1_1") (pintype "passive"))
      (node (ref "R95") (pin "1") (pinfunction "1_1") (pintype "passive"))
      (node (ref "TR2") (pin "1") (pinfunction "P1_1") (pintype "passive"))
      (node (ref "TR2") (pin "2") (pinfunction "P1_2") (pintype "passive"))
      (node (ref "TR2") (pin "5") (pinfunction "NC_5") (pintype "passive"))
      (node (ref "TR3") (pin "1") (pinfunction "P1_1") (pintype "passive"))
      (node (ref "TR3") (pin "2") (pinfunction "P1_2") (pintype "passive"))
      (node (ref "TR3") (pin "5") (pinfunction "NC_5") (pintype "passive"))
    )
    (net (code "37") (name "Net-(C103-Pad2)") (class "Default")
      (node (ref "C103") (pin "2") (pinfunction "2_2") (pintype "passive"))
      (node (ref "R117") (pin "1") (pinfunction "1_1") (pintype "passive"))
    )
    (net (code "38") (name "Net-(C190-Pad2)") (class "Default")
      (node (ref "C190") (pin "2") (pinfunction "2_2") (pintype "passive"))
      (node (ref "R73") (pin "1") (pinfunction "1_1") (pintype "passive"))
      (node (ref "TR3") (pin "3") (pinfunction "P1_3") (pintype "passive"))
    )
    (net (code "39") (name "Net-(C196-Pad2)") (class "Default")
      (node (ref "C196") (pin "2") (pinfunction "2_2") (pintype "passive"))
      (node (ref "R46") (pin "1") (pinfunction "1_1") (pintype "passive"))
      (node (ref "TR2") (pin "3") (pinfunction "P1_3") (pintype "passive"))
    )
    (net (code "40") (name "Net-(IC19-CLK_SEL)") (class "Default")
      (node (ref "IC19") (pin "23") (pinfunction "CLK_SEL_23") (pintype "input"))
      (node (ref "R154") (pin "2") (pinfunction "2_2") (pintype "passive"))
    )
    (net (code "41") (name "Net-(IC19-DIVA)") (class "Default")
      (node (ref "IC19") (pin "1") (pinfunction "DIVA_1") (pintype "input"))
      (node (ref "IC19") (pin "33") (pinfunction "DIVB_33") (pintype "input"))
      (node (ref "R155") (pin "2") (pinfunction "2_2") (pintype "passive"))
    )
    (net (code "42") (name "Net-(IC19-OEA)") (class "Default")
      (node (ref "IC19") (pin "16") (pinfunction "OEA_16") (pintype "input"))
      (node (ref "R103") (pin "2") (pinfunction "2_2") (pintype "passive"))
      (node (ref "R108") (pin "1") (pinfunction "1_1") (pintype "passive"))
    )
    (net (code "43") (name "Net-(IC19-OEB)") (class "Default")
      (node (ref "IC19") (pin "18") (pinfunction "OEB_18") (pintype "input"))
      (node (ref "R109") (pin "2") (pinfunction "2_2") (pintype "passive"))
      (node (ref "R110") (pin "1") (pinfunction "1_1") (pintype "passive"))
    )
    (net (code "44") (name "Net-(IC19-Q0)") (class "Default")
      (node (ref "C57") (pin "2") (pinfunction "2_2") (pintype "passive"))
      (node (ref "IC19") (pin "10") (pinfunction "Q0_10") (pintype "output"))
      (node (ref "R42") (pin "2") (pinfunction "2_2") (pintype "passive"))
    )
    (net (code "45") (name "Net-(IC19-Q1)") (class "Default")
      (node (ref "C59") (pin "2") (pinfunction "2_2") (pintype "passive"))
      (node (ref "IC19") (pin "8") (pinfunction "Q1_8") (pintype "output"))
      (node (ref "R60") (pin "2") (pinfunction "2_2") (pintype "passive"))
    )
    (net (code "46") (name "Net-(IC19-Q2)") (class "Default")
      (node (ref "C62") (pin "2") (pinfunction "2_2") (pintype "passive"))
      (node (ref "IC19") (pin "5") (pinfunction "Q2_5") (pintype "output"))
      (node (ref "R62") (pin "2") (pinfunction "2_2") (pintype "passive"))
    )
    (net (code "47") (name "Net-(IC19-Q3)") (class "Default")
      (node (ref "C92") (pin "2") (pinfunction "2_2") (pintype "passive"))
      (node (ref "IC19") (pin "43") (pinfunction "Q3_43") (pintype "output"))
      (node (ref "R69") (pin "2") (pinfunction "2_2") (pintype "passive"))
    )
    (net (code "48") (name "Net-(IC19-Q5)") (class "Default")
      (node (ref "C56") (pin "2") (pinfunction "2_2") (pintype "passive"))
      (node (ref "IC19") (pin "38") (pinfunction "Q5_38") (pintype "output"))
      (node (ref "R34") (pin "2") (pinfunction "2_2") (pintype "passive"))
    )
    (net (code "49") (name "Net-(IC19-Q6)") (class "Default")
      (node (ref "C65") (pin "2") (pinfunction "2_2") (pintype "passive"))
      (node (ref "IC19") (pin "36") (pinfunction "Q6_36") (pintype "output"))
      (node (ref "R71") (pin "2") (pinfunction "2_2") (pintype "passive"))
    )
    (net (code "50") (name "Net-(IC19-Q7)") (class "Default")
      (node (ref "C68") (pin "2") (pinfunction "2_2") (pintype "passive"))
      (node (ref "IC19") (pin "30") (pinfunction "Q7_30") (pintype "output"))
      (node (ref "R76") (pin "2") (pinfunction "2_2") (pintype "passive"))
    )
    (net (code "51") (name "Net-(IC19-Q8)") (class "Default")
      (node (ref "C95") (pin "2") (pinfunction "2_2") (pintype "passive"))
      (node (ref "IC19") (pin "27") (pinfunction "Q8_27") (pintype "output"))
      (node (ref "R101") (pin "2") (pinfunction "2_2") (pintype "passive"))
    )
    (net (code "52") (name "Net-(IC19-SFOUTA0)") (class "Default")
      (node (ref "IC19") (pin "2") (pinfunction "SFOUTA1_2") (pintype "input"))
      (node (ref "IC19") (pin "3") (pinfunction "SFOUTA0_3") (pintype "input"))
      (node (ref "IC19") (pin "31") (pinfunction "SFOUTB0_31") (pintype "input"))
      (node (ref "IC19") (pin "32") (pinfunction "SFOUTB1_32") (pintype "input"))
      (node (ref "R141") (pin "2") (pinfunction "2_2") (pintype "passive"))
    )
    (net (code "53") (name "Net-(IC19-VDD)") (class "Default")
      (node (ref "C100") (pin "2") (pinfunction "2_2") (pintype "passive"))
      (node (ref "C91") (pin "2") (pinfunction "2_2") (pintype "passive"))
      (node (ref "C97") (pin "2") (pinfunction "2_2") (pintype "passive"))
      (node (ref "C98") (pin "2") (pinfunction "2_2") (pintype "passive"))
      (node (ref "IC19") (pin "12") (pinfunction "VDD_12") (pintype "power_in"))
      (node (ref "IC19") (pin "34") (pinfunction "VDDOB_34") (pintype "power_in"))
      (node (ref "IC19") (pin "44") (pinfunction "VDDOA_44") (pintype "power_in"))
      (node (ref "L14") (pin "1") (pinfunction "1_1") (pintype "passive"))
      (node (ref "R103") (pin "1") (pinfunction "1_1") (pintype "passive"))
      (node (ref "R109") (pin "1") (pinfunction "1_1") (pintype "passive"))
      (node (ref "R151") (pin "2") (pinfunction "2_2") (pintype "passive"))
    )
    (net (code "54") (name "Net-(IC19-VREF)") (class "Default")
      (node (ref "C94") (pin "2") (pinfunction "2_2") (pintype "passive"))
      (node (ref "IC19") (pin "17") (pinfunction "VREF_17") (pintype "output"))
    )
    (net (code "55") (name "Net-(IC19-~{Q0})") (class "Default")
      (node (ref "C58") (pin "2") (pinfunction "2_2") (pintype "passive"))
      (node (ref "IC19") (pin "9") (pinfunction "~{Q0}_9") (pintype "output"))
      (node (ref "R37") (pin "2") (pinfunction "2_2") (pintype "passive"))
    )
    (net (code "56") (name "Net-(IC19-~{Q1})") (class "Default")
      (node (ref "C60") (pin "2") (pinfunction "2_2") (pintype "passive"))
      (node (ref "IC19") (pin "7") (pinfunction "~{Q1}_7") (pintype "output"))
      (node (ref "R61") (pin "2") (pinfunction "2_2") (pintype "passive"))
    )
    (net (code "57") (name "Net-(IC19-~{Q2})") (class "Default")
      (node (ref "C88") (pin "2") (pinfunction "2_2") (pintype "passive"))
      (node (ref "IC19") (pin "4") (pinfunction "~{Q2}_4") (pintype "output"))
      (node (ref "R63") (pin "2") (pinfunction "2_2") (pintype "passive"))
    )
    (net (code "58") (name "Net-(IC19-~{Q3})") (class "Default")
      (node (ref "C93") (pin "2") (pinfunction "2_2") (pintype "passive"))
      (node (ref "IC19") (pin "42") (pinfunction "~{Q3}_42") (pintype "output"))
      (node (ref "R77") (pin "2") (pinfunction "2_2") (pintype "passive"))
    )
    (net (code "59") (name "Net-(IC19-~{Q5})") (class "Default")
      (node (ref "C61") (pin "2") (pinfunction "2_2") (pintype "passive"))
      (node (ref "IC19") (pin "37") (pinfunction "~{Q5}_37") (pintype "output"))
      (node (ref "R70") (pin "2") (pinfunction "2_2") (pintype "passive"))
    )
    (net (code "60") (name "Net-(IC19-~{Q6})") (class "Default")
      (node (ref "C66") (pin "2") (pinfunction "2_2") (pintype "passive"))
      (node (ref "IC19") (pin "35") (pinfunction "~{Q6}_35") (pintype "output"))
      (node (ref "R72") (pin "2") (pinfunction "2_2") (pintype "passive"))
    )
    (net (code "61") (name "Net-(IC19-~{Q7})") (class "Default")
      (node (ref "C71") (pin "2") (pinfunction "2_2") (pintype "passive"))
      (node (ref "IC19") (pin "29") (pinfunction "~{Q7}_29") (pintype "output"))
      (node (ref "R95") (pin "2") (pinfunction "2_2") (pintype "passive"))
    )
    (net (code "62") (name "Net-(IC19-~{Q8})") (class "Default")
      (node (ref "C96") (pin "2") (pinfunction "2_2") (pintype "passive"))
      (node (ref "IC19") (pin "26") (pinfunction "~{Q8}_26") (pintype "output"))
      (node (ref "R102") (pin "2") (pinfunction "2_2") (pintype "passive"))
    )
    (net (code "63") (name "Net-(IC24-CLK_SEL)") (class "Default")
      (node (ref "IC24") (pin "2") (pinfunction "CLK_SEL_2") (pintype "input"))
      (node (ref "R165") (pin "2") (pinfunction "2_2") (pintype "passive"))
    )
    (net (code "64") (name "Net-(IC24-VDD)") (class "Default")
      (node (ref "C123") (pin "2") (pinfunction "2_2") (pintype "passive"))
      (node (ref "C131") (pin "2") (pinfunction "2_2") (pintype "passive"))
      (node (ref "IC24") (pin "5") (pinfunction "VDD_5") (pintype "power_in"))
      (node (ref "L10") (pin "1") (pinfunction "1_1") (pintype "passive"))
      (node (ref "R164") (pin "2") (pinfunction "2_2") (pintype "passive"))
    )
    (net (code "65") (name "Net-(IC24-~{CLK0})") (class "Default")
      (node (ref "C122") (pin "1") (pinfunction "1_1") (pintype "passive"))
      (node (ref "IC24") (pin "7") (pinfunction "~{CLK0}_7") (pintype "input"))
      (node (ref "R162") (pin "2") (pinfunction "2_2") (pintype "passive"))
    )
    (net (code "66") (name "Net-(IC25-IN+)") (class "Default")
      (node (ref "IC25") (pin "1") (pinfunction "IN+_1") (pintype "input"))
      (node (ref "R186") (pin "1") (pinfunction "1_1") (pintype "passive"))
      (node (ref "R188") (pin "2") (pinfunction "2_2") (pintype "passive"))
      (node (ref "R189") (pin "2") (pinfunction "2_2") (pintype "passive"))
    )
    (net (code "67") (name "Net-(IC25-IN-)") (class "Default")
      (node (ref "IC25") (pin "3") (pinfunction "IN-_3") (pintype "input"))
      (node (ref "R183") (pin "2") (pinfunction "2_2") (pintype "passive"))
      (node (ref "R184") (pin "2") (pinfunction "2_2") (pintype "passive"))
      (node (ref "R185") (pin "1") (pinfunction "1_1") (pintype "passive"))
    )
    (net (code "68") (name "Net-(IC25-OUT)") (class "Default")
      (node (ref "IC25") (pin "4") (pinfunction "OUT_4") (pintype "output"))
      (node (ref "R183") (pin "1") (pinfunction "1_1") (pintype "passive"))
      (node (ref "R184") (pin "1") (pinfunction "1_1") (pintype "passive"))
      (node (ref "R187") (pin "2") (pinfunction "2_2") (pintype "passive"))
    )
    (net (code "69") (name "Net-(IC25-V+)") (class "Default")
      (node (ref "C101") (pin "2") (pinfunction "2_2") (pintype "passive"))
      (node (ref "C102") (pin "2") (pinfunction "2_2") (pintype "passive"))
      (node (ref "C212") (pin "1") (pinfunction "1_1") (pintype "passive"))
      (node (ref "IC25") (pin "5") (pinfunction "V+_5") (pintype "power_in"))
      (node (ref "L9") (pin "1") (pinfunction "1_1") (pintype "passive"))
      (node (ref "OSC1") (pin "4") (pinfunction "VDD_4") (pintype "power_in"))
      (node (ref "OSC2") (pin "1") (pinfunction "OE_1") (pintype "passive"))
      (node (ref "OSC2") (pin "4") (pinfunction "VDD_4") (pintype "passive"))
      (node (ref "R167") (pin "2") (pinfunction "2_2") (pintype "passive"))
      (node (ref "R188") (pin "1") (pinfunction "1_1") (pintype "passive"))
    )
    (net (code "70") (name "Net-(J9-Pad1)") (class "Default")
      (node (ref "J9") (pin "1") (pinfunction "1_1") (pintype "bidirectional"))
      (node (ref "R186") (pin "2") (pinfunction "2_2") (pintype "passive"))
      (node (ref "R191") (pin "1") (pinfunction "1_1") (pintype "passive"))
    )
    (net (code "71") (name "Net-(J9-Pad2)") (class "Default")
      (node (ref "J9") (pin "2") (pinfunction "2_2") (pintype "bidirectional"))
      (node (ref "R185") (pin "2") (pinfunction "2_2") (pintype "passive"))
      (node (ref "R190") (pin "1") (pinfunction "1_1") (pintype "passive"))
    )
    (net (code "72") (name "Net-(OSC1-NC)") (class "Default")
      (node (ref "C145") (pin "2") (pinfunction "2_2") (pintype "passive"))
      (node (ref "OSC1") (pin "1") (pinfunction "NC_1") (pintype "passive"))
      (node (ref "R167") (pin "1") (pinfunction "1_1") (pintype "passive"))
      (node (ref "R168") (pin "2") (pinfunction "2_2") (pintype "passive"))
      (node (ref "R187") (pin "1") (pinfunction "1_1") (pintype "passive"))
      (node (ref "R191") (pin "2") (pinfunction "2_2") (pintype "passive"))
    )
    (net (code "73") (name "Net-(OSC1-OUT)") (class "Default")
      (node (ref "OSC1") (pin "3") (pinfunction "OUT_3") (pintype "output"))
      (node (ref "OSC2") (pin "3") (pinfunction "CLK_3") (pintype "passive"))
      (node (ref "R117") (pin "2") (pinfunction "2_2") (pintype "passive"))
    )
    (net (code "74") (name "Net-(T1-D)") (class "Default")
      (node (ref "L9") (pin "2") (pinfunction "2_2") (pintype "passive"))
      (node (ref "T1") (pin "3") (pinfunction "D_3") (pintype "passive"))
    )
    (net (code "75") (name "P1V8A") (class "Default")
      (node (ref "R151") (pin "1") (pinfunction "1_1") (pintype "passive"))
      (node (ref "R164") (pin "1") (pinfunction "1_1") (pintype "passive"))
    )
    (net (code "76") (name "P3V3A") (class "Default")
      (node (ref "L10") (pin "2") (pinfunction "2_2") (pintype "passive"))
      (node (ref "L14") (pin "2") (pinfunction "2_2") (pintype "passive"))
      (node (ref "T1") (pin "2") (pinfunction "S_2") (pintype "passive"))
    )
    (net (code "77") (name "unconnected-(IC19-NC-Pad11)") (class "Default")
      (node (ref "IC19") (pin "11") (pinfunction "NC_11") (pintype "passive+no_connect"))
    )
    (net (code "78") (name "unconnected-(IC19-NC-Pad13)") (class "Default")
      (node (ref "IC19") (pin "13") (pinfunction "NC_13") (pintype "passive+no_connect"))
    )
    (net (code "79") (name "unconnected-(IC19-NC-Pad21)") (class "Default")
      (node (ref "IC19") (pin "21") (pinfunction "NC_21") (pintype "passive+no_connect"))
    )
    (net (code "80") (name "unconnected-(IC19-NC-Pad28)") (class "Default")
      (node (ref "IC19") (pin "28") (pinfunction "NC_28") (pintype "passive+no_connect"))
    )
    (net (code "81") (name "unconnected-(IC19-Q4-Pad41)") (class "Default")
      (node (ref "IC19") (pin "41") (pinfunction "Q4_41") (pintype "output+no_connect"))
    )
    (net (code "82") (name "unconnected-(IC19-Q9-Pad25)") (class "Default")
      (node (ref "IC19") (pin "25") (pinfunction "Q9_25") (pintype "output+no_connect"))
    )
    (net (code "83") (name "unconnected-(IC19-~{Q4}-Pad40)") (class "Default")
      (node (ref "IC19") (pin "40") (pinfunction "~{Q4}_40") (pintype "output+no_connect"))
    )
    (net (code "84") (name "unconnected-(IC19-~{Q9}-Pad24)") (class "Default")
      (node (ref "IC19") (pin "24") (pinfunction "~{Q9}_24") (pintype "output+no_connect"))
    )
    (net (code "85") (name "unconnected-(IC24-Q1-Pad11)") (class "Default")
      (node (ref "IC24") (pin "11") (pinfunction "Q1_11") (pintype "output+no_connect"))
    )
    (net (code "86") (name "unconnected-(IC24-Q2-Pad13)") (class "Default")
      (node (ref "IC24") (pin "13") (pinfunction "Q2_13") (pintype "output+no_connect"))
    )
    (net (code "87") (name "unconnected-(IC24-Q3-Pad15)") (class "Default")
      (node (ref "IC24") (pin "15") (pinfunction "Q3_15") (pintype "output+no_connect"))
    )
    (net (code "88") (name "unconnected-(IC24-~{Q1}-Pad12)") (class "Default")
      (node (ref "IC24") (pin "12") (pinfunction "~{Q1}_12") (pintype "output+no_connect"))
    )
    (net (code "89") (name "unconnected-(IC24-~{Q2}-Pad14)") (class "Default")
      (node (ref "IC24") (pin "14") (pinfunction "~{Q2}_14") (pintype "output+no_connect"))
    )
    (net (code "90") (name "unconnected-(IC24-~{Q3}-Pad16)") (class "Default")
      (node (ref "IC24") (pin "16") (pinfunction "~{Q3}_16") (pintype "output+no_connect"))
    )
    (net (code "91") (name "unconnected-(J10-Pad3)") (class "Default")
      (node (ref "J10") (pin "3") (pinfunction "3_3") (pintype "bidirectional"))
    )
    (net (code "92") (name "unconnected-(J10-Pad4)") (class "Default")
      (node (ref "J10") (pin "4") (pinfunction "4_4") (pintype "bidirectional"))
    )
    (net (code "93") (name "unconnected-(J10-Pad5)") (class "Default")
      (node (ref "J10") (pin "5") (pinfunction "5_5") (pintype "bidirectional"))
    )
    (net (code "94") (name "unconnected-(J10-Pad6)") (class "Default")
      (node (ref "J10") (pin "6") (pinfunction "6_6") (pintype "bidirectional"))
    )
    (net (code "95") (name "unconnected-(J10-Pad9)") (class "Default")
      (node (ref "J10") (pin "9") (pinfunction "9_9") (pintype "bidirectional"))
    )
    (net (code "96") (name "unconnected-(J10-Pad10)") (class "Default")
      (node (ref "J10") (pin "10") (pinfunction "10_10") (pintype "bidirectional"))
    )
    (net (code "97") (name "unconnected-(J10-Pad11)") (class "Default")
      (node (ref "J10") (pin "11") (pinfunction "11_11") (pintype "bidirectional"))
    )
    (net (code "98") (name "unconnected-(J10-Pad12)") (class "Default")
      (node (ref "J10") (pin "12") (pinfunction "12_12") (pintype "bidirectional"))
    )
    (net (code "99") (name "unconnected-(J10-Pad16)") (class "Default")
      (node (ref "J10") (pin "16") (pinfunction "16_16") (pintype "bidirectional"))
    )
    (net (code "100") (name "unconnected-(J10-Pad18)") (class "Default")
      (node (ref "J10") (pin "18") (pinfunction "18_18") (pintype "bidirectional"))
    )
  )
)
